# LowDroneBoard.net
KiCad netlist of a schematic drawn in EAGLE
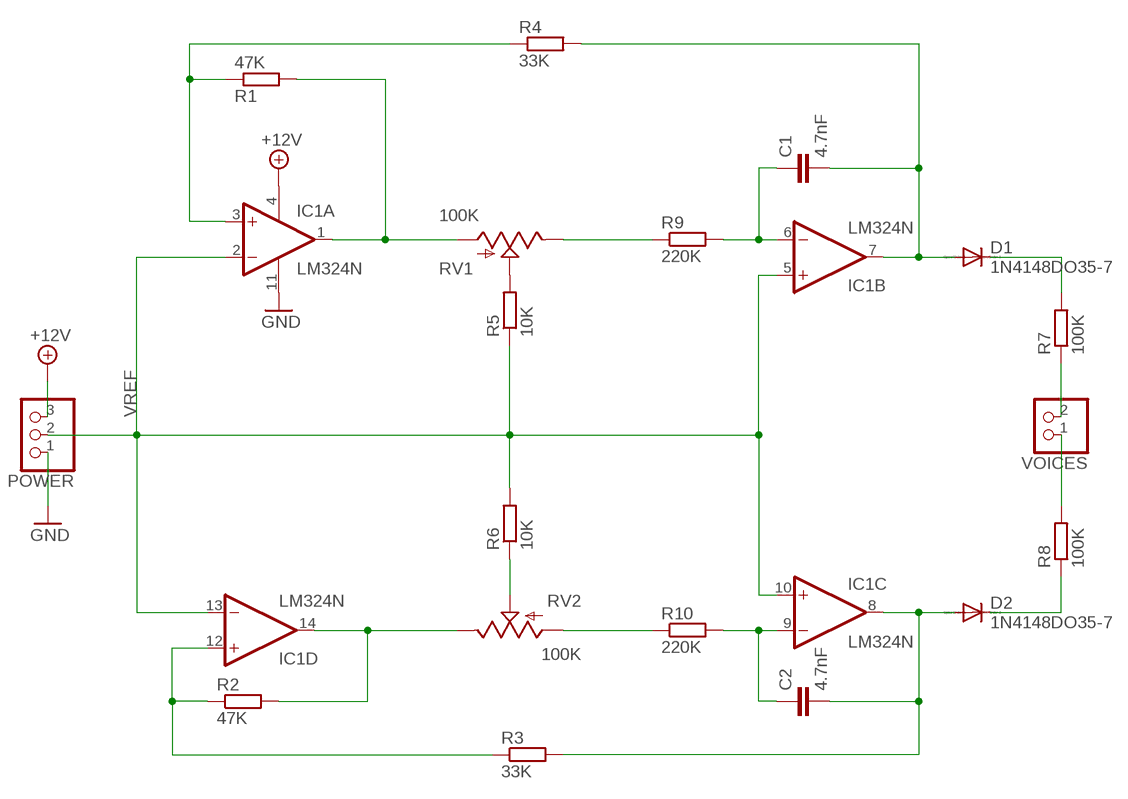
[diagram p0: schematic, sheet 1]

(export (version "E")
  (design (tool "Eeschema 10.0.6"))
  (components
    (comp (ref "C1")
      (value "4.7nF")
      (footprint "eagle-import:CAP-PTH-SMALL")
      (libsource (lib "eagle-import") (part "CAPPTH"))
    )
    (comp (ref "C2")
      (value "4.7nF")
      (footprint "eagle-import:CAP-PTH-SMALL")
      (libsource (lib "eagle-import") (part "CAPPTH"))
    )
    (comp (ref "D1")
      (value "1N4148DO35-7")
      (footprint "eagle-import:DO35-7")
      (libsource (lib "eagle-import") (part "1N4148DO35-7"))
    )
    (comp (ref "D2")
      (value "1N4148DO35-7")
      (footprint "eagle-import:DO35-7")
      (libsource (lib "eagle-import") (part "1N4148DO35-7"))
    )
    (comp (ref "IC1")
      (value "LM324N")
      (footprint "eagle-import:DIL14")
      (libsource (lib "eagle-import") (part "LM324N"))
    )
    (comp (ref "POWER")
      (value "PINHD-1X3/90")
      (footprint "eagle-import:1X03_90")
      (libsource (lib "eagle-import") (part "PINHD-1X3/90"))
    )
    (comp (ref "R1")
      (value "47K")
      (footprint "eagle-import:0207_7")
      (libsource (lib "eagle-import") (part "R-EU_0207/7"))
    )
    (comp (ref "R2")
      (value "47K")
      (footprint "eagle-import:0207_7")
      (libsource (lib "eagle-import") (part "R-EU_0207/7"))
    )
    (comp (ref "R3")
      (value "33K")
      (footprint "eagle-import:0207_7")
      (libsource (lib "eagle-import") (part "R-EU_0207/7"))
    )
    (comp (ref "R4")
      (value "33K")
      (footprint "eagle-import:0207_7")
      (libsource (lib "eagle-import") (part "R-EU_0207/7"))
    )
    (comp (ref "R5")
      (value "10K")
      (footprint "eagle-import:0207_7")
      (libsource (lib "eagle-import") (part "R-EU_0207/7"))
    )
    (comp (ref "R6")
      (value "10K")
      (footprint "eagle-import:0207_7")
      (libsource (lib "eagle-import") (part "R-EU_0207/7"))
    )
    (comp (ref "R7")
      (value "100K")
      (footprint "eagle-import:0207_7")
      (libsource (lib "eagle-import") (part "R-EU_0207/7"))
    )
    (comp (ref "R8")
      (value "100K")
      (footprint "eagle-import:0207_7")
      (libsource (lib "eagle-import") (part "R-EU_0207/7"))
    )
    (comp (ref "R9")
      (value "220K")
      (footprint "eagle-import:0207_7")
      (libsource (lib "eagle-import") (part "R-EU_0207/7"))
    )
    (comp (ref "R10")
      (value "220K")
      (footprint "eagle-import:0207_7")
      (libsource (lib "eagle-import") (part "R-EU_0207/7"))
    )
    (comp (ref "RV1")
      (value "100K")
      (footprint "eagle-import:POT_ALPHA_RV16AF-20")
      (libsource (lib "eagle-import") (part "POT-RV16AF-20"))
    )
    (comp (ref "RV2")
      (value "100K")
      (footprint "eagle-import:POT_ALPHA_RV16AF-20")
      (libsource (lib "eagle-import") (part "POT-RV16AF-20"))
    )
    (comp (ref "VOICES")
      (value "PINHD-1X2/90")
      (footprint "eagle-import:1X02_90")
      (libsource (lib "eagle-import") (part "PINHD-1X2/90"))
    )
  )
  (nets
    (net (code "1") (name "+12V") (class "Default")
      (node (ref "IC1") (pin "4") (pinfunction "V+_4") (pintype "power_in"))
      (node (ref "POWER") (pin "3") (pinfunction "3_3") (pintype "passive"))
    )
    (net (code "2") (name "/VREF") (class "Default")
      (node (ref "IC1") (pin "10") (pinfunction "+IN_10") (pintype "input"))
      (node (ref "IC1") (pin "13") (pinfunction "-IN_13") (pintype "input"))
      (node (ref "IC1") (pin "2") (pinfunction "-IN_2") (pintype "input"))
      (node (ref "IC1") (pin "5") (pinfunction "+IN_5") (pintype "input"))
      (node (ref "POWER") (pin "2") (pinfunction "2_2") (pintype "passive"))
      (node (ref "R5") (pin "1") (pinfunction "1_1") (pintype "passive"))
      (node (ref "R6") (pin "2") (pinfunction "2_2") (pintype "passive"))
    )
    (net (code "3") (name "GND") (class "Default")
      (node (ref "IC1") (pin "11") (pinfunction "V-_11") (pintype "power_in"))
      (node (ref "POWER") (pin "1") (pinfunction "1_1") (pintype "passive"))
    )
    (net (code "4") (name "Net-(D1-PadC)") (class "Default")
      (node (ref "D1") (pin "C") (pinfunction "C_C") (pintype "passive"))
      (node (ref "R7") (pin "2") (pinfunction "2_2") (pintype "passive"))
    )
    (net (code "5") (name "Net-(D2-PadC)") (class "Default")
      (node (ref "D2") (pin "C") (pinfunction "C_C") (pintype "passive"))
      (node (ref "R8") (pin "1") (pinfunction "1_1") (pintype "passive"))
    )
    (net (code "6") (name "Net-(IC1A-+IN)") (class "Default")
      (node (ref "IC1") (pin "3") (pinfunction "+IN_3") (pintype "input"))
      (node (ref "R1") (pin "1") (pinfunction "1_1") (pintype "passive"))
      (node (ref "R4") (pin "1") (pinfunction "1_1") (pintype "passive"))
    )
    (net (code "7") (name "Net-(IC1A-OUT)") (class "Default")
      (node (ref "IC1") (pin "1") (pinfunction "OUT_1") (pintype "output"))
      (node (ref "R1") (pin "2") (pinfunction "2_2") (pintype "passive"))
      (node (ref "RV1") (pin "1") (pinfunction "A_1") (pintype "passive"))
    )
    (net (code "8") (name "Net-(IC1B--IN)") (class "Default")
      (node (ref "C1") (pin "1") (pinfunction "1_1") (pintype "passive"))
      (node (ref "IC1") (pin "6") (pinfunction "-IN_6") (pintype "input"))
      (node (ref "R9") (pin "2") (pinfunction "2_2") (pintype "passive"))
    )
    (net (code "9") (name "Net-(IC1B-OUT)") (class "Default")
      (node (ref "C1") (pin "2") (pinfunction "2_2") (pintype "passive"))
      (node (ref "D1") (pin "A") (pinfunction "A_A") (pintype "passive"))
      (node (ref "IC1") (pin "7") (pinfunction "OUT_7") (pintype "output"))
      (node (ref "R4") (pin "2") (pinfunction "2_2") (pintype "passive"))
    )
    (net (code "10") (name "Net-(IC1C--IN)") (class "Default")
      (node (ref "C2") (pin "1") (pinfunction "1_1") (pintype "passive"))
      (node (ref "IC1") (pin "9") (pinfunction "-IN_9") (pintype "input"))
      (node (ref "R10") (pin "2") (pinfunction "2_2") (pintype "passive"))
    )
    (net (code "11") (name "Net-(IC1C-OUT)") (class "Default")
      (node (ref "C2") (pin "2") (pinfunction "2_2") (pintype "passive"))
      (node (ref "D2") (pin "A") (pinfunction "A_A") (pintype "passive"))
      (node (ref "IC1") (pin "8") (pinfunction "OUT_8") (pintype "output"))
      (node (ref "R3") (pin "2") (pinfunction "2_2") (pintype "passive"))
    )
    (net (code "12") (name "Net-(IC1D-+IN)") (class "Default")
      (node (ref "IC1") (pin "12") (pinfunction "+IN_12") (pintype "input"))
      (node (ref "R2") (pin "1") (pinfunction "1_1") (pintype "passive"))
      (node (ref "R3") (pin "1") (pinfunction "1_1") (pintype "passive"))
    )
    (net (code "13") (name "Net-(IC1D-OUT)") (class "Default")
      (node (ref "IC1") (pin "14") (pinfunction "OUT_14") (pintype "output"))
      (node (ref "R2") (pin "2") (pinfunction "2_2") (pintype "passive"))
      (node (ref "RV2") (pin "3") (pinfunction "E_3") (pintype "passive"))
    )
    (net (code "14") (name "Net-(R7-Pad1)") (class "Default")
      (node (ref "R7") (pin "1") (pinfunction "1_1") (pintype "passive"))
      (node (ref "VOICES") (pin "2") (pinfunction "2_2") (pintype "passive"))
    )
    (net (code "15") (name "Net-(R8-Pad2)") (class "Default")
      (node (ref "R8") (pin "2") (pinfunction "2_2") (pintype "passive"))
      (node (ref "VOICES") (pin "1") (pinfunction "1_1") (pintype "passive"))
    )
    (net (code "16") (name "Net-(RV1-E)") (class "Default")
      (node (ref "R9") (pin "1") (pinfunction "1_1") (pintype "passive"))
      (node (ref "RV1") (pin "3") (pinfunction "E_3") (pintype "passive"))
    )
    (net (code "17") (name "Net-(RV1-S)") (class "Default")
      (node (ref "R5") (pin "2") (pinfunction "2_2") (pintype "passive"))
      (node (ref "RV1") (pin "2") (pinfunction "S_2") (pintype "passive"))
    )
    (net (code "18") (name "Net-(RV2-A)") (class "Default")
      (node (ref "R10") (pin "1") (pinfunction "1_1") (pintype "passive"))
      (node (ref "RV2") (pin "1") (pinfunction "A_1") (pintype "passive"))
    )
    (net (code "19") (name "Net-(RV2-S)") (class "Default")
      (node (ref "R6") (pin "1") (pinfunction "1_1") (pintype "passive"))
      (node (ref "RV2") (pin "2") (pinfunction "S_2") (pintype "passive"))
    )
  )
)
